# GNSS_PPS_LED_Driver.net
KiCad netlist of a schematic drawn in Altium Designer
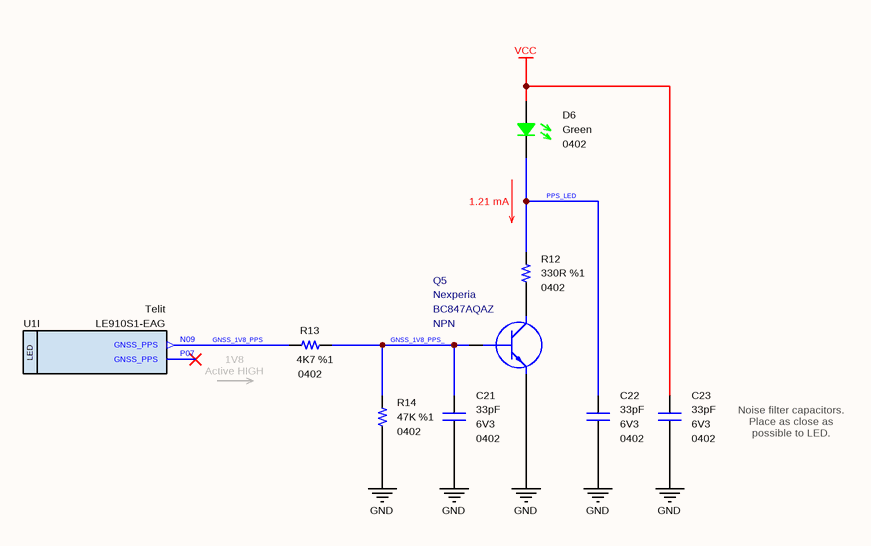
[diagram p0: GNSS PPS LED Driver.SchDoc]

(export (version "E")
  (design (tool "Eeschema 10.0.6"))
  (components
    (comp (ref "C21")
      (value "33pF")
      (footprint "CAPACITOR_0402")
      (description "Capacitor - 33pF [0402] (Ceramic)")
      (fields
        (field (name "CASE") "0402")
        (field (name "VOLTAGE") "6V3")
        (field (name "MANUFACTURER PART NUMBER") "C0402C330J9RACAUTO")
        (field (name "TOLERANCE") "10%")
      )
      (libsource (lib "P101DA_Library") (part "33pF [0402-6V3]"))
    )
    (comp (ref "C22")
      (value "33pF")
      (footprint "CAPACITOR_0402")
      (description "Capacitor - 33pF [0402] (Ceramic)")
      (fields
        (field (name "CASE") "0402")
        (field (name "VOLTAGE") "6V3")
        (field (name "MANUFACTURER PART NUMBER") "C0402C330J9RACAUTO")
        (field (name "TOLERANCE") "10%")
      )
      (libsource (lib "P101DA_Library") (part "33pF [0402-6V3]"))
    )
    (comp (ref "C23")
      (value "33pF")
      (footprint "CAPACITOR_0402")
      (description "Capacitor - 33pF [0402] (Ceramic)")
      (fields
        (field (name "CASE") "0402")
        (field (name "VOLTAGE") "6V3")
        (field (name "MANUFACTURER PART NUMBER") "C0402C330J9RACAUTO")
        (field (name "TOLERANCE") "10%")
      )
      (libsource (lib "P101DA_Library") (part "33pF [0402-6V3]"))
    )
    (comp (ref "D6")
      (value "~")
      (footprint "LED_0402")
      (description "Standard LEDs - SMD MINI-MOLD ULTRA COMPACT GREEN")
      (fields
        (field (name "MANUFACTURER PART NUMBER") "SML-P12MTT86R")
        (field (name "CASE") "0402")
        (field (name "COLOR") "Green")
      )
      (libsource (lib "P101DA_Library") (part "LED (0402-Green)"))
    )
    (comp (ref "Q5")
      (value "~")
      (footprint "SOT1215")
      (description "Bipolar NPN Transistors")
      (fields
        (field (name "POLARITY") "NPN")
        (field (name "MANUFACTURER PART NUMBER") "BC847AQAZ")
        (field (name "MANUFACTURER NAME") "Nexperia")
      )
      (libsource (lib "P101DA_Library") (part "BC847"))
    )
    (comp (ref "R12")
      (value "330R")
      (footprint "RESISTOR_0402")
      (description "Thick Film Resistors - SMD 1/16 W 330 Ohm 1%")
      (fields
        (field (name "CASE") "0402")
        (field (name "MANUFACTURER PART NUMBER") "CRCW0402330RFKED")
        (field (name "TOLERANCE") "%1")
      )
      (libsource (lib "P101DA_Library") (part "330R"))
    )
    (comp (ref "R13")
      (value "4K7")
      (footprint "RESISTOR_0402")
      (description "Thick Film Resistors - SMD 1/16 W 4.7 Kohms 1%")
      (fields
        (field (name "CASE") "0402")
        (field (name "MANUFACTURER PART NUMBER") "CRCW04024K70FKED")
        (field (name "TOLERANCE") "%1")
      )
      (libsource (lib "P101DA_Library") (part "4K7"))
    )
    (comp (ref "R14")
      (value "47K")
      (footprint "RESISTOR_0402")
      (description "Thick Film Resistors - SMD 1/16 W 47 Kohms 1%")
      (fields
        (field (name "CASE") "0402")
        (field (name "MANUFACTURER PART NUMBER") "CRCW040247K0FKED")
        (field (name "TOLERANCE") "%1")
      )
      (libsource (lib "P101DA_Library") (part "47K"))
    )
    (comp (ref "U1")
      (value "LE910S1-EAG LTE GSM Module")
      (footprint "LE910 GSM Modem")
      (description "Telit LE910S1-EAG GPRS/GNSS Module")
      (fields
        (field (name "MANUFACTURER PART NUMBER") "LE910S1-EAG")
        (field (name "MANUFACTURER NAME") "Telit")
      )
      (libsource (lib "P101DA_Library") (part "IC - LE910S1-EAG"))
    )
  )
  (nets
    (net (code "1") (name "/GNSS_1V8_PPS") (class "Default")
      (node (ref "R13") (pin "2") (pinfunction "2_2") (pintype "passive"))
      (node (ref "U1") (pin "N09") (pinfunction "GNSS_PPS_N09") (pintype "output"))
    )
    (net (code "2") (name "/GNSS_1V8_PPS_") (class "Default")
      (node (ref "C21") (pin "2") (pinfunction "2_2") (pintype "passive"))
      (node (ref "Q5") (pin "1") (pinfunction "B_1") (pintype "passive"))
      (node (ref "R13") (pin "1") (pinfunction "1_1") (pintype "passive"))
      (node (ref "R14") (pin "2") (pinfunction "2_2") (pintype "passive"))
    )
    (net (code "3") (name "/PPS_LED") (class "Default")
      (node (ref "C22") (pin "2") (pinfunction "2_2") (pintype "passive"))
      (node (ref "D6") (pin "1") (pinfunction "1_1") (pintype "passive"))
      (node (ref "R12") (pin "2") (pinfunction "2_2") (pintype "passive"))
    )
    (net (code "4") (name "GND") (class "Default")
      (node (ref "C21") (pin "1") (pinfunction "1_1") (pintype "passive"))
      (node (ref "C22") (pin "1") (pinfunction "1_1") (pintype "passive"))
      (node (ref "C23") (pin "1") (pinfunction "1_1") (pintype "passive"))
      (node (ref "Q5") (pin "2") (pinfunction "E_2") (pintype "passive"))
      (node (ref "R14") (pin "1") (pinfunction "1_1") (pintype "passive"))
    )
    (net (code "5") (name "Net-(Q5-C)") (class "Default")
      (node (ref "Q5") (pin "3") (pinfunction "C_3") (pintype "passive"))
      (node (ref "R12") (pin "1") (pinfunction "1_1") (pintype "passive"))
    )
    (net (code "6") (name "VCC") (class "Default")
      (node (ref "C23") (pin "2") (pinfunction "2_2") (pintype "passive"))
      (node (ref "D6") (pin "2") (pinfunction "2_2") (pintype "passive"))
    )
    (net (code "7") (name "unconnected-(U1I-GNSS_PPS-PadP07)") (class "Default")
      (node (ref "U1") (pin "P07") (pinfunction "GNSS_PPS_P07") (pintype "passive+no_connect"))
    )
  )
)
